# JBC_PD_USB.net
KiCad netlist of a schematic drawn in Altium Designer
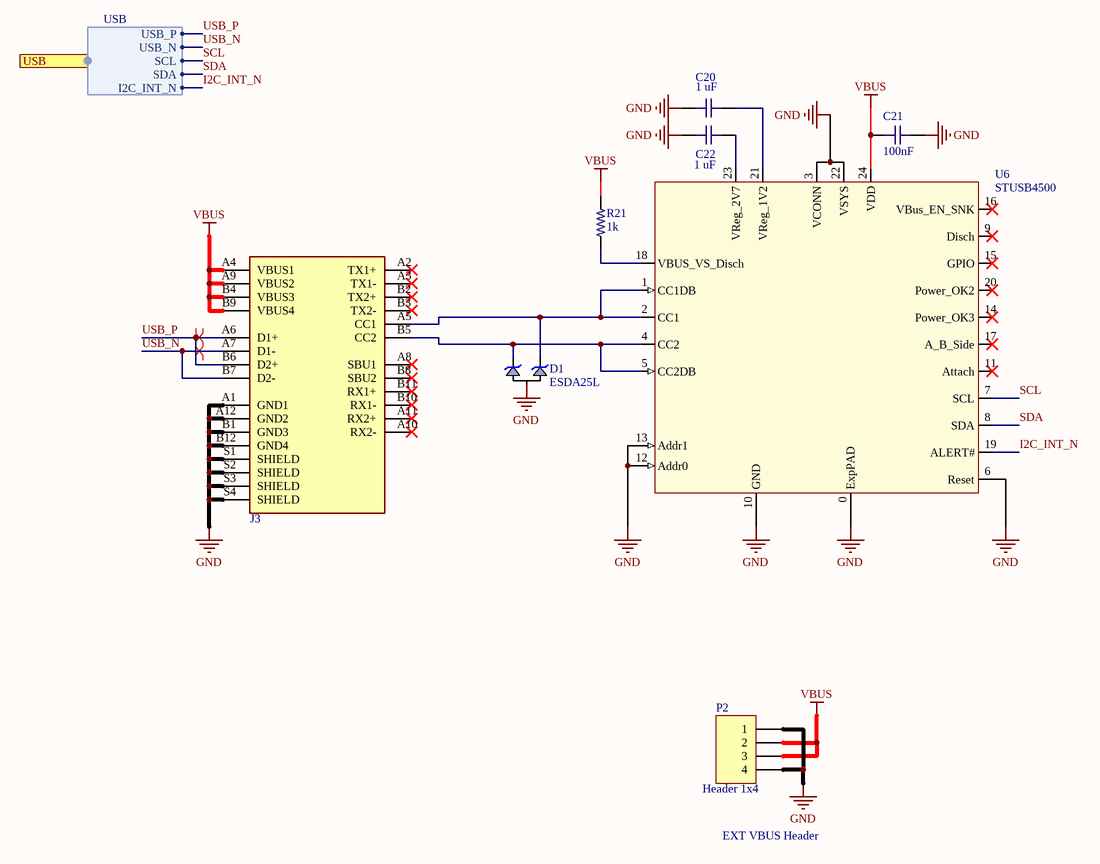
[diagram p0: JBC_PD_USB.SchDoc]

(export (version "E")
  (design (tool "Eeschema 10.0.6"))
  (components
    (comp (ref "C20")
      (value "1 uF")
      (footprint "C0603-IPC")
      (description "Chip Capacitor, 0603, 1uF +/- 0.1uF, 10V, X7R")
      (fields (field (name "Comment") "C0603 1uF 10V X7R"))
      (libsource (lib "Capacitors") (part "C0603 1uF 10V X7R"))
    )
    (comp (ref "C21")
      (value "100nF")
      (footprint "C0603-IPC")
      (description "Chip Capacitor, 0603, 100nF, 25V, X7R")
      (fields (field (name "Comment") "C0603 100nF 25V X7R"))
      (libsource (lib "Capacitors") (part "C0603 100nF 25V X7R"))
    )
    (comp (ref "C22")
      (value "1 uF")
      (footprint "C0603-IPC")
      (description "Chip Capacitor, 0603, 1uF +/- 0.1uF, 10V, X7R")
      (fields (field (name "Comment") "C0603 1uF 10V X7R"))
      (libsource (lib "Capacitors") (part "C0603 1uF 10V X7R"))
    )
    (comp (ref "D1")
      (value "ESDA25L")
      (footprint "SOT23-3L")
      (description "Dual Transil Array For ESD Protection in SOT23-3 Vbr = 25V")
      (fields (field (name "MANUFACTURER") "STMicroelectronics"))
      (libsource (lib "Diodes") (part "ESDA25L"))
    )
    (comp (ref "J3")
      (value "USB C")
      (footprint "Molex USB-C")
      (fields
        (field (name "MF") "Molex")
        (field (name "DIGI-KEY_PART_NUMBER") "WM12856CT-ND")
        (field (name "MP") "1054500101")
      )
      (libsource (lib "Connectors") (part "USB C"))
    )
    (comp (ref "P2")
      (value "Header 1x4")
      (footprint "HEADER 1X4 SMD 2.54mm")
      (description "Header, 4-Pin")
      (fields (field (name "PUBLISHER") "Altium Limited"))
      (libsource (lib "Connectors") (part "Header 1x4"))
    )
    (comp (ref "R21")
      (value "1k")
      (footprint "R0603-IPC")
      (description "RES SMD 1K OHM 1% 1/10W 0603")
      (fields (field (name "TOLERANCE") "±1%") (field (name "Comment") "R0603 1K 1%"))
      (libsource (lib "Resistors") (part "R0603 1K 1%"))
    )
    (comp (ref "U6")
      (value "STUSB4500")
      (footprint "Integrated Circuits:QFN24 - 4X4MM - PITCH 0.5MM - EXPOSEDPAD")
      (description "Standalone USB PD controller  with SINK auto-run mode in QFN24 4x4mm")
      (fields (field (name "MANUFACTURER") "STMicroelectronics"))
      (libsource (lib "Integrated Circuits") (part "STUSB4500QTR"))
    )
  )
  (nets
    (net (code "2") (name "/I2C_INT_N") (class "Default")
      (node (ref "U6") (pin "19") (pinfunction "ALERT#_19") (pintype "open_collector"))
    )
    (net (code "3") (name "/SCL") (class "Default")
      (node (ref "U6") (pin "7") (pinfunction "SCL_7") (pintype "passive"))
    )
    (net (code "4") (name "/SDA") (class "Default")
      (node (ref "U6") (pin "8") (pinfunction "SDA_8") (pintype "passive"))
    )
    (net (code "5") (name "/USB_N") (class "Default")
      (node (ref "J3") (pin "A7") (pinfunction "D1-_A7") (pintype "passive"))
      (node (ref "J3") (pin "B7") (pinfunction "D2-_B7") (pintype "passive"))
    )
    (net (code "6") (name "/USB_P") (class "Default")
      (node (ref "J3") (pin "A6") (pinfunction "D1+_A6") (pintype "passive"))
      (node (ref "J3") (pin "B6") (pinfunction "D2+_B6") (pintype "passive"))
    )
    (net (code "8") (name "GND") (class "Default")
      (node (ref "C20") (pin "1") (pintype "passive"))
      (node (ref "C21") (pin "2") (pintype "passive"))
      (node (ref "C22") (pin "1") (pintype "passive"))
      (node (ref "D1") (pin "3") (pinfunction "A_3") (pintype "passive"))
      (node (ref "J3") (pin "A1") (pinfunction "GND1_A1") (pintype "passive"))
      (node (ref "J3") (pin "A12") (pinfunction "GND2_A12") (pintype "passive"))
      (node (ref "J3") (pin "B1") (pinfunction "GND3_B1") (pintype "passive"))
      (node (ref "J3") (pin "B12") (pinfunction "GND4_B12") (pintype "passive"))
      (node (ref "J3") (pin "S1") (pinfunction "SHIELD_S1") (pintype "passive"))
      (node (ref "J3") (pin "S2") (pinfunction "SHIELD_S2") (pintype "passive"))
      (node (ref "J3") (pin "S3") (pinfunction "SHIELD_S3") (pintype "passive"))
      (node (ref "J3") (pin "S4") (pinfunction "SHIELD_S4") (pintype "passive"))
      (node (ref "P2") (pin "1") (pinfunction "1_1") (pintype "passive"))
      (node (ref "P2") (pin "4") (pinfunction "4_4") (pintype "passive"))
      (node (ref "U6") (pin "0") (pinfunction "ExpPAD_0") (pintype "passive"))
      (node (ref "U6") (pin "10") (pinfunction "GND_10") (pintype "passive"))
      (node (ref "U6") (pin "12") (pinfunction "Addr0_12") (pintype "input"))
      (node (ref "U6") (pin "13") (pinfunction "Addr1_13") (pintype "input"))
      (node (ref "U6") (pin "22") (pinfunction "VSYS_22") (pintype "passive"))
      (node (ref "U6") (pin "3") (pinfunction "VCONN_3") (pintype "passive"))
      (node (ref "U6") (pin "6") (pinfunction "Reset_6") (pintype "passive"))
    )
    (net (code "9") (name "Net-(D1-K1)") (class "Default")
      (node (ref "D1") (pin "1") (pinfunction "K1_1") (pintype "passive"))
      (node (ref "J3") (pin "A5") (pinfunction "CC1_A5") (pintype "passive"))
      (node (ref "U6") (pin "1") (pinfunction "CC1DB_1") (pintype "input"))
      (node (ref "U6") (pin "2") (pinfunction "CC1_2") (pintype "bidirectional"))
    )
    (net (code "10") (name "Net-(D1-K2)") (class "Default")
      (node (ref "D1") (pin "2") (pinfunction "K2_2") (pintype "power_in"))
      (node (ref "J3") (pin "B5") (pinfunction "CC2_B5") (pintype "passive"))
      (node (ref "U6") (pin "4") (pinfunction "CC2_4") (pintype "bidirectional"))
      (node (ref "U6") (pin "5") (pinfunction "CC2DB_5") (pintype "input"))
    )
    (net (code "11") (name "Net-(U6-VBUS_VS_Disch)") (class "Default")
      (node (ref "R21") (pin "1") (pintype "passive"))
      (node (ref "U6") (pin "18") (pinfunction "VBUS_VS_Disch_18") (pintype "passive"))
    )
    (net (code "12") (name "Net-(U6-VReg_1V2)") (class "Default")
      (node (ref "C20") (pin "2") (pintype "passive"))
      (node (ref "U6") (pin "21") (pinfunction "VReg_1V2_21") (pintype "passive"))
    )
    (net (code "13") (name "Net-(U6-VReg_2V7)") (class "Default")
      (node (ref "C22") (pin "2") (pintype "passive"))
      (node (ref "U6") (pin "23") (pinfunction "VReg_2V7_23") (pintype "passive"))
    )
    (net (code "14") (name "VBUS") (class "Default")
      (node (ref "C21") (pin "1") (pintype "passive"))
      (node (ref "J3") (pin "A4") (pinfunction "VBUS1_A4") (pintype "passive"))
      (node (ref "J3") (pin "A9") (pinfunction "VBUS2_A9") (pintype "passive"))
      (node (ref "J3") (pin "B4") (pinfunction "VBUS3_B4") (pintype "passive"))
      (node (ref "J3") (pin "B9") (pinfunction "VBUS4_B9") (pintype "passive"))
      (node (ref "P2") (pin "2") (pinfunction "2_2") (pintype "passive"))
      (node (ref "P2") (pin "3") (pinfunction "3_3") (pintype "passive"))
      (node (ref "R21") (pin "2") (pintype "passive"))
      (node (ref "U6") (pin "24") (pinfunction "VDD_24") (pintype "passive"))
    )
    (net (code "15") (name "unconnected-(J3-RX1+-PadB11)") (class "Default")
      (node (ref "J3") (pin "B11") (pinfunction "RX1+_B11") (pintype "passive+no_connect"))
    )
    (net (code "16") (name "unconnected-(J3-RX1--PadB10)") (class "Default")
      (node (ref "J3") (pin "B10") (pinfunction "RX1-_B10") (pintype "passive+no_connect"))
    )
    (net (code "17") (name "unconnected-(J3-RX2+-PadA11)") (class "Default")
      (node (ref "J3") (pin "A11") (pinfunction "RX2+_A11") (pintype "passive+no_connect"))
    )
    (net (code "18") (name "unconnected-(J3-RX2--PadA10)") (class "Default")
      (node (ref "J3") (pin "A10") (pinfunction "RX2-_A10") (pintype "passive+no_connect"))
    )
    (net (code "19") (name "unconnected-(J3-SBU1-PadA8)") (class "Default")
      (node (ref "J3") (pin "A8") (pinfunction "SBU1_A8") (pintype "passive+no_connect"))
    )
    (net (code "20") (name "unconnected-(J3-SBU2-PadB8)") (class "Default")
      (node (ref "J3") (pin "B8") (pinfunction "SBU2_B8") (pintype "passive+no_connect"))
    )
    (net (code "21") (name "unconnected-(J3-TX1+-PadA2)") (class "Default")
      (node (ref "J3") (pin "A2") (pinfunction "TX1+_A2") (pintype "passive+no_connect"))
    )
    (net (code "22") (name "unconnected-(J3-TX1--PadA3)") (class "Default")
      (node (ref "J3") (pin "A3") (pinfunction "TX1-_A3") (pintype "passive+no_connect"))
    )
    (net (code "23") (name "unconnected-(J3-TX2+-PadB2)") (class "Default")
      (node (ref "J3") (pin "B2") (pinfunction "TX2+_B2") (pintype "passive+no_connect"))
    )
    (net (code "24") (name "unconnected-(J3-TX2--PadB3)") (class "Default")
      (node (ref "J3") (pin "B3") (pinfunction "TX2-_B3") (pintype "passive+no_connect"))
    )
    (net (code "25") (name "unconnected-(U6-A_B_Side-Pad17)") (class "Default")
      (node (ref "U6") (pin "17") (pinfunction "A_B_Side_17") (pintype "open_collector+no_connect"))
    )
    (net (code "26") (name "unconnected-(U6-Attach-Pad11)") (class "Default")
      (node (ref "U6") (pin "11") (pinfunction "Attach_11") (pintype "open_collector+no_connect"))
    )
    (net (code "27") (name "unconnected-(U6-Disch-Pad9)") (class "Default")
      (node (ref "U6") (pin "9") (pinfunction "Disch_9") (pintype "open_collector+no_connect"))
    )
    (net (code "28") (name "unconnected-(U6-GPIO-Pad15)") (class "Default")
      (node (ref "U6") (pin "15") (pinfunction "GPIO_15") (pintype "open_collector+no_connect"))
    )
    (net (code "29") (name "unconnected-(U6-Power_OK2-Pad20)") (class "Default")
      (node (ref "U6") (pin "20") (pinfunction "Power_OK2_20") (pintype "open_collector+no_connect"))
    )
    (net (code "30") (name "unconnected-(U6-Power_OK3-Pad14)") (class "Default")
      (node (ref "U6") (pin "14") (pinfunction "Power_OK3_14") (pintype "open_collector+no_connect"))
    )
    (net (code "31") (name "unconnected-(U6-VBus_EN_SNK-Pad16)") (class "Default")
      (node (ref "U6") (pin "16") (pinfunction "VBus_EN_SNK_16") (pintype "open_collector+no_connect"))
    )
  )
)
